# FPGA_SDRAM_bank.net
KiCad netlist of a schematic drawn in Altium Designer
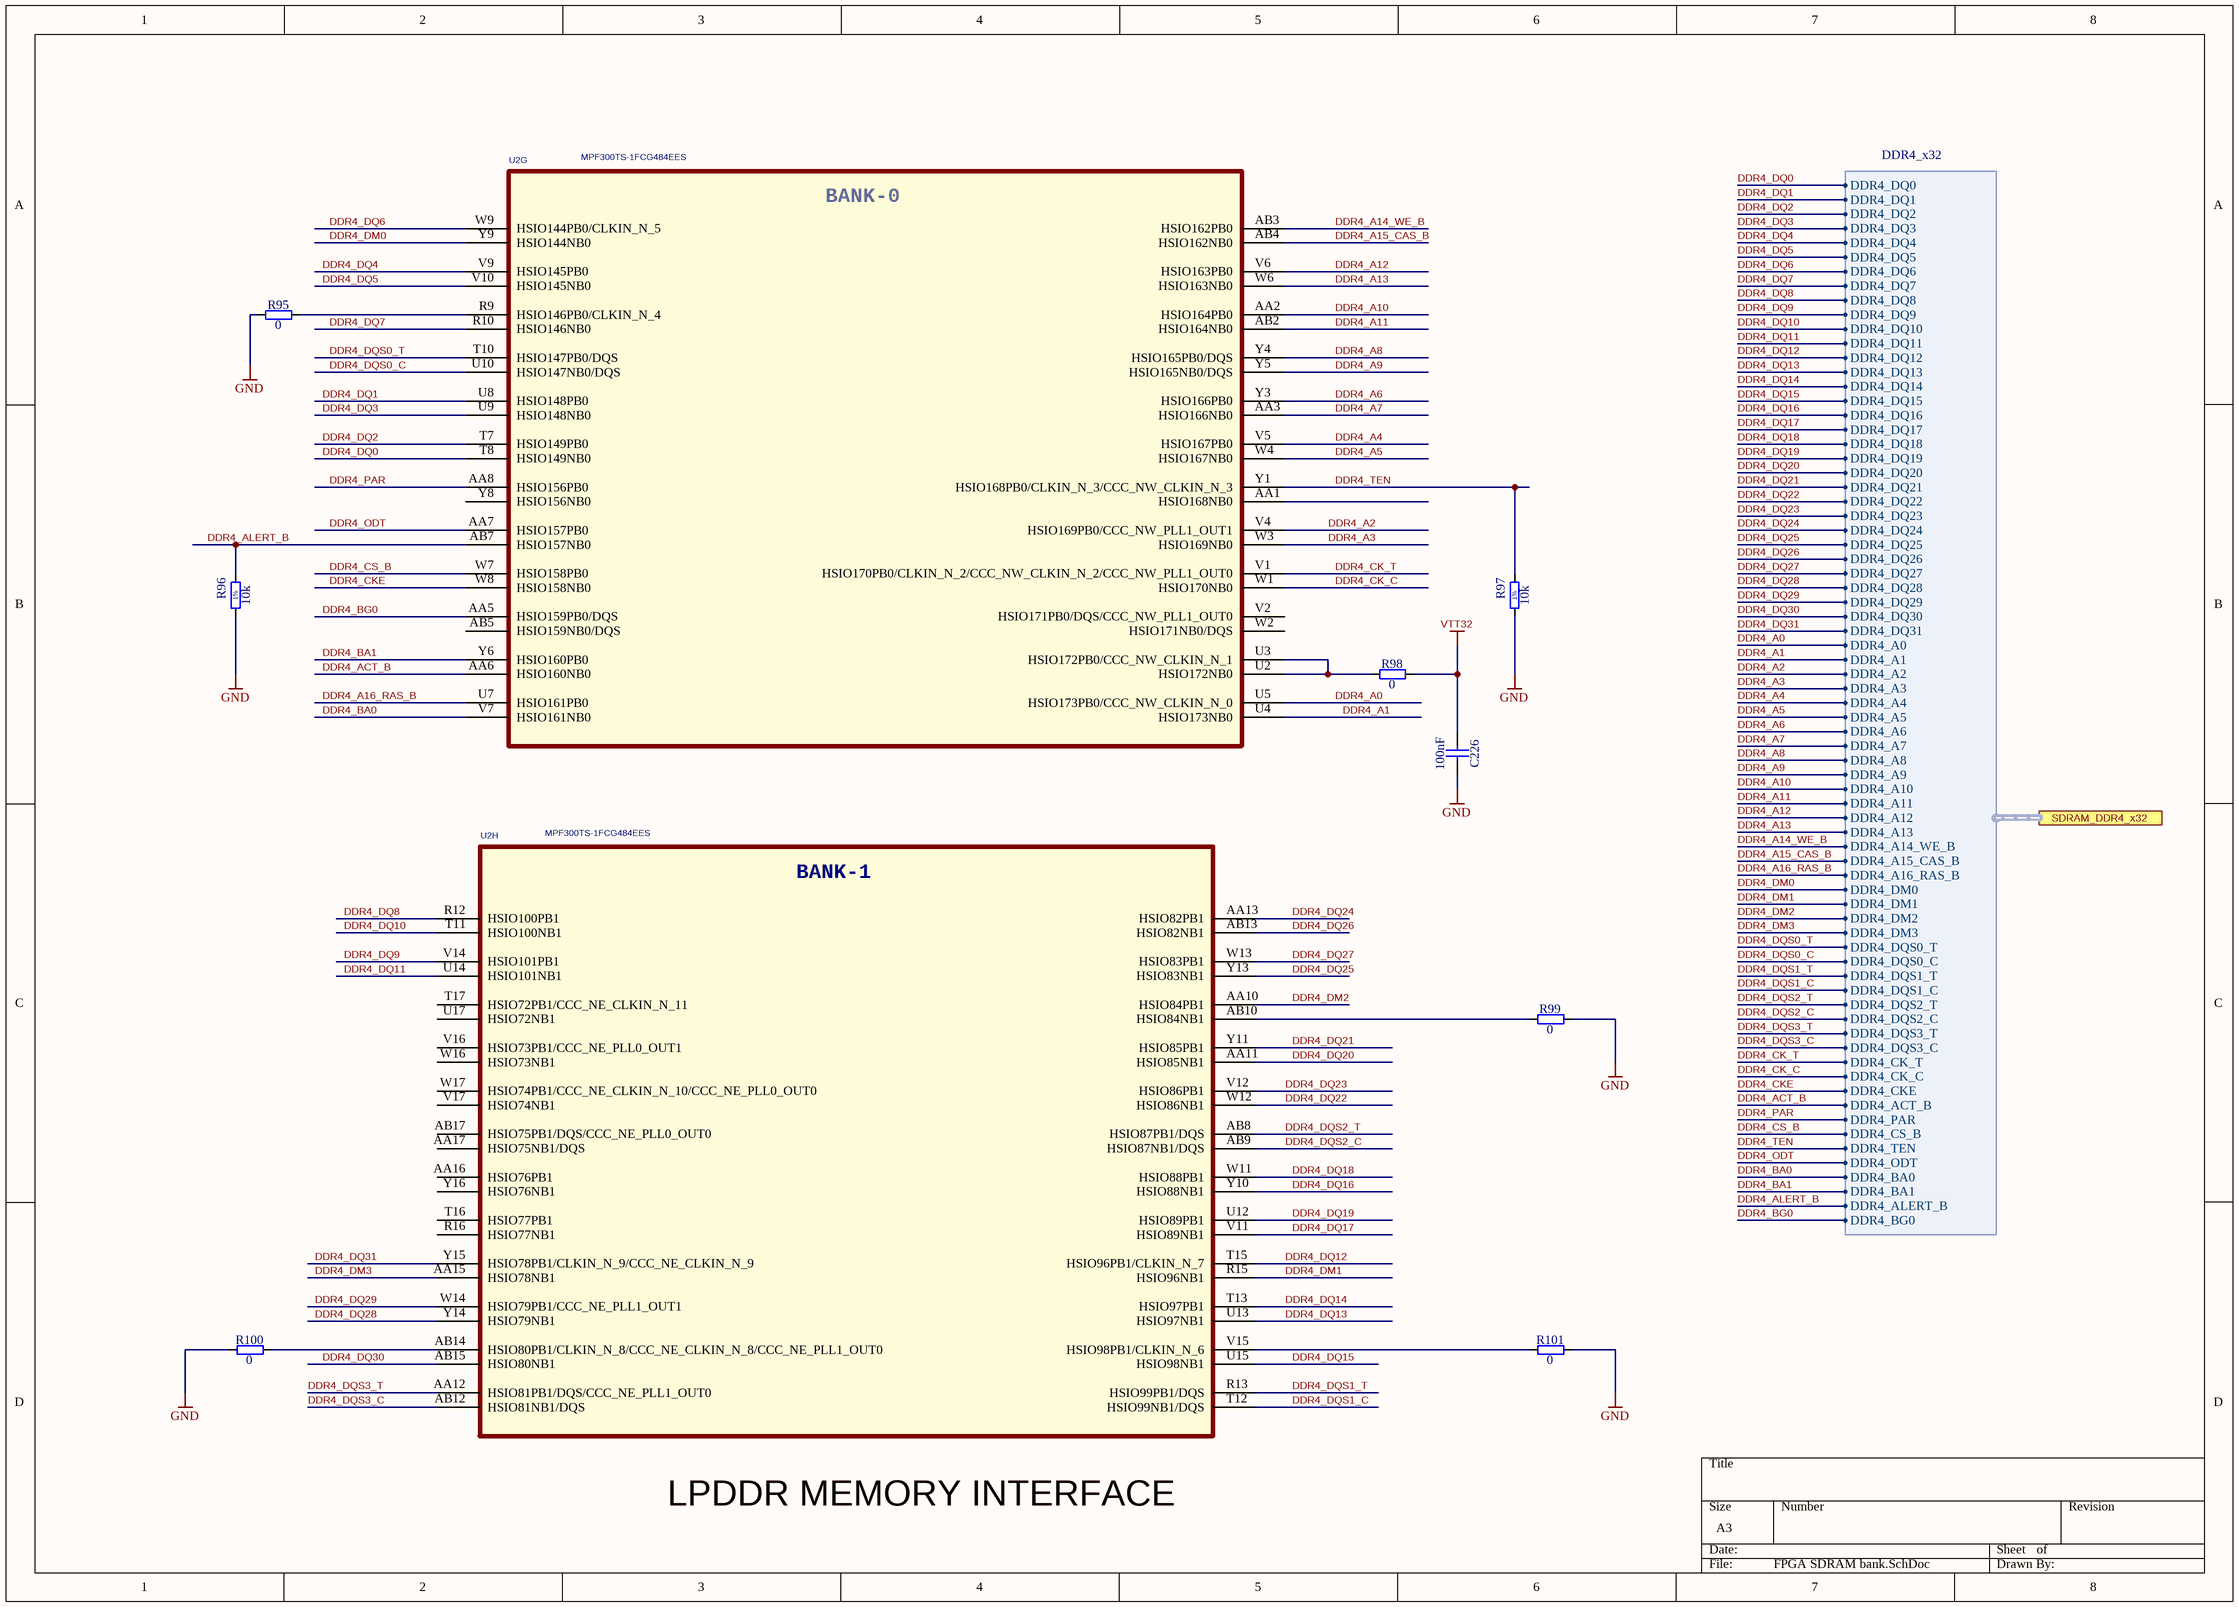
[diagram p0: FPGA SDRAM bank.SchDoc]

(export (version "E")
  (design (tool "Eeschema 10.0.6"))
  (components
    (comp (ref "C226")
      (value "100nF")
      (footprint "CAPC0603X33N")
      (description "Non-polarised capacitor")
      (fields
        (field (name "MANUFACTURER PART NUMBER") "CC0201_100NF_6.3V_10%_X5R")
        (field (name "MANUFACTURER") "GENERIC")
        (field (name "AUTHOR") "CERN DEM JLC")
      )
      (libsource (lib "Capacitors") (part "Capacitor - non polarized"))
    )
    (comp (ref "R95")
      (value "0")
      (footprint "RESC1005X40N")
      (description "Resistor")
      (fields
        (field (name "PART NUMBER") "R0402_0R_JUMPER")
        (field (name "MANUFACTURER") "GENERIC")
        (field (name "AUTHOR") "CERN DEM JLC")
      )
      (libsource (lib "Resistors") (part "Resistor"))
    )
    (comp (ref "R96")
      (value "10k")
      (footprint "RESC1005X40N")
      (description "Resistor - 1%")
      (fields
        (field (name "MANUFACTURER PART NUMBER") "R0402_10K_1%_0.0625W_100PPM")
        (field (name "MANUFACTURER") "GENERIC")
        (field (name "AUTHOR") "CERN DEM JLC")
      )
      (libsource (lib "Resistors") (part "Resistor - 1%"))
    )
    (comp (ref "R97")
      (value "10k")
      (footprint "RESC1005X40N")
      (description "Resistor - 1%")
      (fields
        (field (name "MANUFACTURER PART NUMBER") "R0402_10K_1%_0.0625W_100PPM")
        (field (name "MANUFACTURER") "GENERIC")
        (field (name "AUTHOR") "CERN DEM JLC")
      )
      (libsource (lib "Resistors") (part "Resistor - 1%"))
    )
    (comp (ref "R98")
      (value "0")
      (footprint "RESC1005X40N")
      (description "Resistor")
      (fields
        (field (name "PART NUMBER") "R0402_0R_JUMPER")
        (field (name "MANUFACTURER") "GENERIC")
        (field (name "AUTHOR") "CERN DEM JLC")
      )
      (libsource (lib "Resistors") (part "Resistor"))
    )
    (comp (ref "R99")
      (value "0")
      (footprint "RESC1005X40N")
      (description "Resistor")
      (fields
        (field (name "PART NUMBER") "R0402_0R_JUMPER")
        (field (name "MANUFACTURER") "GENERIC")
        (field (name "AUTHOR") "CERN DEM JLC")
      )
      (libsource (lib "Resistors") (part "Resistor"))
    )
    (comp (ref "R100")
      (value "0")
      (footprint "RESC1005X40N")
      (description "Resistor")
      (fields
        (field (name "PART NUMBER") "R0402_0R_JUMPER")
        (field (name "MANUFACTURER") "GENERIC")
        (field (name "AUTHOR") "CERN DEM JLC")
      )
      (libsource (lib "Resistors") (part "Resistor"))
    )
    (comp (ref "R101")
      (value "0")
      (footprint "RESC1005X40N")
      (description "Resistor")
      (fields
        (field (name "PART NUMBER") "R0402_0R_JUMPER")
        (field (name "MANUFACTURER") "GENERIC")
        (field (name "AUTHOR") "CERN DEM JLC")
      )
      (libsource (lib "Resistors") (part "Resistor"))
    )
    (comp (ref "U2")
      (value "MPF300TS-1FCG484EES")
      (footprint "BGA484C100P22X22_2300X2300X320")
      (description "FCG484,23mmX23mm,1.0mm pitch")
      (fields (field (name "MANUFACTURER") "Microsemi") (field (name "PART NUMBER") "MPF300TS-1FCG484I"))
      (libsource (lib "LIBRARY_SCH") (part "FPGA_MPF300T-FCG484"))
    )
  )
  (nets
    (net (code "2") (name "/DDR4_A0") (class "Default")
      (node (ref "U2") (pin "U5") (pinfunction "HSIO173PB0/CCC_NW_CLKIN_N_0_U5") (pintype "passive"))
    )
    (net (code "3") (name "/DDR4_A1") (class "Default")
      (node (ref "U2") (pin "U4") (pinfunction "HSIO173NB0_U4") (pintype "passive"))
    )
    (net (code "4") (name "/DDR4_A2") (class "Default")
      (node (ref "U2") (pin "V4") (pinfunction "HSIO169PB0/CCC_NW_PLL1_OUT1_V4") (pintype "passive"))
    )
    (net (code "5") (name "/DDR4_A3") (class "Default")
      (node (ref "U2") (pin "W3") (pinfunction "HSIO169NB0_W3") (pintype "passive"))
    )
    (net (code "6") (name "/DDR4_A4") (class "Default")
      (node (ref "U2") (pin "V5") (pinfunction "HSIO167PB0_V5") (pintype "passive"))
    )
    (net (code "7") (name "/DDR4_A5") (class "Default")
      (node (ref "U2") (pin "W4") (pinfunction "HSIO167NB0_W4") (pintype "passive"))
    )
    (net (code "8") (name "/DDR4_A6") (class "Default")
      (node (ref "U2") (pin "Y3") (pinfunction "HSIO166PB0_Y3") (pintype "passive"))
    )
    (net (code "9") (name "/DDR4_A7") (class "Default")
      (node (ref "U2") (pin "AA3") (pinfunction "HSIO166NB0_AA3") (pintype "passive"))
    )
    (net (code "10") (name "/DDR4_A8") (class "Default")
      (node (ref "U2") (pin "Y4") (pinfunction "HSIO165PB0/DQS_Y4") (pintype "passive"))
    )
    (net (code "11") (name "/DDR4_A9") (class "Default")
      (node (ref "U2") (pin "Y5") (pinfunction "HSIO165NB0/DQS_Y5") (pintype "passive"))
    )
    (net (code "12") (name "/DDR4_A10") (class "Default")
      (node (ref "U2") (pin "AA2") (pinfunction "HSIO164PB0_AA2") (pintype "passive"))
    )
    (net (code "13") (name "/DDR4_A11") (class "Default")
      (node (ref "U2") (pin "AB2") (pinfunction "HSIO164NB0_AB2") (pintype "passive"))
    )
    (net (code "14") (name "/DDR4_A12") (class "Default")
      (node (ref "U2") (pin "V6") (pinfunction "HSIO163PB0_V6") (pintype "passive"))
    )
    (net (code "15") (name "/DDR4_A13") (class "Default")
      (node (ref "U2") (pin "W6") (pinfunction "HSIO163NB0_W6") (pintype "passive"))
    )
    (net (code "16") (name "/DDR4_A14_WE_B") (class "Default")
      (node (ref "U2") (pin "AB3") (pinfunction "HSIO162PB0_AB3") (pintype "passive"))
    )
    (net (code "17") (name "/DDR4_A15_CAS_B") (class "Default")
      (node (ref "U2") (pin "AB4") (pinfunction "HSIO162NB0_AB4") (pintype "passive"))
    )
    (net (code "18") (name "/DDR4_A16_RAS_B") (class "Default")
      (node (ref "U2") (pin "U7") (pinfunction "HSIO161PB0_U7") (pintype "passive"))
    )
    (net (code "19") (name "/DDR4_ACT_B") (class "Default")
      (node (ref "U2") (pin "AA6") (pinfunction "HSIO160NB0_AA6") (pintype "passive"))
    )
    (net (code "20") (name "/DDR4_ALERT_B") (class "Default")
      (node (ref "R96") (pin "2") (pinfunction "2_2") (pintype "passive"))
      (node (ref "U2") (pin "AB7") (pinfunction "HSIO157NB0_AB7") (pintype "passive"))
    )
    (net (code "21") (name "/DDR4_BA0") (class "Default")
      (node (ref "U2") (pin "V7") (pinfunction "HSIO161NB0_V7") (pintype "passive"))
    )
    (net (code "22") (name "/DDR4_BA1") (class "Default")
      (node (ref "U2") (pin "Y6") (pinfunction "HSIO160PB0_Y6") (pintype "passive"))
    )
    (net (code "23") (name "/DDR4_BG0") (class "Default")
      (node (ref "U2") (pin "AA5") (pinfunction "HSIO159PB0/DQS_AA5") (pintype "passive"))
    )
    (net (code "24") (name "/DDR4_CKE") (class "Default")
      (node (ref "U2") (pin "W8") (pinfunction "HSIO158NB0_W8") (pintype "passive"))
    )
    (net (code "25") (name "/DDR4_CK_C") (class "Default")
      (node (ref "U2") (pin "W1") (pinfunction "HSIO170NB0_W1") (pintype "passive"))
    )
    (net (code "26") (name "/DDR4_CK_T") (class "Default")
      (node (ref "U2") (pin "V1") (pinfunction "HSIO170PB0/CLKIN_N_2/CCC_NW_CLKIN_N_2/CCC_NW_PLL1_OUT0_V1") (pintype "passive"))
    )
    (net (code "27") (name "/DDR4_CS_B") (class "Default")
      (node (ref "U2") (pin "W7") (pinfunction "HSIO158PB0_W7") (pintype "passive"))
    )
    (net (code "28") (name "/DDR4_DM0") (class "Default")
      (node (ref "U2") (pin "Y9") (pinfunction "HSIO144NB0_Y9") (pintype "passive"))
    )
    (net (code "29") (name "/DDR4_DM1") (class "Default")
      (node (ref "U2") (pin "R15") (pinfunction "HSIO96NB1_R15") (pintype "passive"))
    )
    (net (code "30") (name "/DDR4_DM2") (class "Default")
      (node (ref "U2") (pin "AA10") (pinfunction "HSIO84PB1_AA10") (pintype "passive"))
    )
    (net (code "31") (name "/DDR4_DM3") (class "Default")
      (node (ref "U2") (pin "AA15") (pinfunction "HSIO78NB1_AA15") (pintype "passive"))
    )
    (net (code "32") (name "/DDR4_DQ0") (class "Default")
      (node (ref "U2") (pin "T8") (pinfunction "HSIO149NB0_T8") (pintype "passive"))
    )
    (net (code "33") (name "/DDR4_DQ1") (class "Default")
      (node (ref "U2") (pin "U8") (pinfunction "HSIO148PB0_U8") (pintype "passive"))
    )
    (net (code "34") (name "/DDR4_DQ2") (class "Default")
      (node (ref "U2") (pin "T7") (pinfunction "HSIO149PB0_T7") (pintype "passive"))
    )
    (net (code "35") (name "/DDR4_DQ3") (class "Default")
      (node (ref "U2") (pin "U9") (pinfunction "HSIO148NB0_U9") (pintype "passive"))
    )
    (net (code "36") (name "/DDR4_DQ4") (class "Default")
      (node (ref "U2") (pin "V9") (pinfunction "HSIO145PB0_V9") (pintype "passive"))
    )
    (net (code "37") (name "/DDR4_DQ5") (class "Default")
      (node (ref "U2") (pin "V10") (pinfunction "HSIO145NB0_V10") (pintype "passive"))
    )
    (net (code "38") (name "/DDR4_DQ6") (class "Default")
      (node (ref "U2") (pin "W9") (pinfunction "HSIO144PB0/CLKIN_N_5_W9") (pintype "passive"))
    )
    (net (code "39") (name "/DDR4_DQ7") (class "Default")
      (node (ref "U2") (pin "R10") (pinfunction "HSIO146NB0_R10") (pintype "passive"))
    )
    (net (code "40") (name "/DDR4_DQ8") (class "Default")
      (node (ref "U2") (pin "R12") (pinfunction "HSIO100PB1_R12") (pintype "passive"))
    )
    (net (code "41") (name "/DDR4_DQ9") (class "Default")
      (node (ref "U2") (pin "V14") (pinfunction "HSIO101PB1_V14") (pintype "passive"))
    )
    (net (code "42") (name "/DDR4_DQ10") (class "Default")
      (node (ref "U2") (pin "T11") (pinfunction "HSIO100NB1_T11") (pintype "passive"))
    )
    (net (code "43") (name "/DDR4_DQ11") (class "Default")
      (node (ref "U2") (pin "U14") (pinfunction "HSIO101NB1_U14") (pintype "passive"))
    )
    (net (code "44") (name "/DDR4_DQ12") (class "Default")
      (node (ref "U2") (pin "T15") (pinfunction "HSIO96PB1/CLKIN_N_7_T15") (pintype "passive"))
    )
    (net (code "45") (name "/DDR4_DQ13") (class "Default")
      (node (ref "U2") (pin "U13") (pinfunction "HSIO97NB1_U13") (pintype "passive"))
    )
    (net (code "46") (name "/DDR4_DQ14") (class "Default")
      (node (ref "U2") (pin "T13") (pinfunction "HSIO97PB1_T13") (pintype "passive"))
    )
    (net (code "47") (name "/DDR4_DQ15") (class "Default")
      (node (ref "U2") (pin "U15") (pinfunction "HSIO98NB1_U15") (pintype "passive"))
    )
    (net (code "48") (name "/DDR4_DQ16") (class "Default")
      (node (ref "U2") (pin "Y10") (pinfunction "HSIO88NB1_Y10") (pintype "passive"))
    )
    (net (code "49") (name "/DDR4_DQ17") (class "Default")
      (node (ref "U2") (pin "V11") (pinfunction "HSIO89NB1_V11") (pintype "passive"))
    )
    (net (code "50") (name "/DDR4_DQ18") (class "Default")
      (node (ref "U2") (pin "W11") (pinfunction "HSIO88PB1_W11") (pintype "passive"))
    )
    (net (code "51") (name "/DDR4_DQ19") (class "Default")
      (node (ref "U2") (pin "U12") (pinfunction "HSIO89PB1_U12") (pintype "passive"))
    )
    (net (code "52") (name "/DDR4_DQ20") (class "Default")
      (node (ref "U2") (pin "AA11") (pinfunction "HSIO85NB1_AA11") (pintype "passive"))
    )
    (net (code "53") (name "/DDR4_DQ21") (class "Default")
      (node (ref "U2") (pin "Y11") (pinfunction "HSIO85PB1_Y11") (pintype "passive"))
    )
    (net (code "54") (name "/DDR4_DQ22") (class "Default")
      (node (ref "U2") (pin "W12") (pinfunction "HSIO86NB1_W12") (pintype "passive"))
    )
    (net (code "55") (name "/DDR4_DQ23") (class "Default")
      (node (ref "U2") (pin "V12") (pinfunction "HSIO86PB1_V12") (pintype "passive"))
    )
    (net (code "56") (name "/DDR4_DQ24") (class "Default")
      (node (ref "U2") (pin "AA13") (pinfunction "HSIO82PB1_AA13") (pintype "passive"))
    )
    (net (code "57") (name "/DDR4_DQ25") (class "Default")
      (node (ref "U2") (pin "Y13") (pinfunction "HSIO83NB1_Y13") (pintype "passive"))
    )
    (net (code "58") (name "/DDR4_DQ26") (class "Default")
      (node (ref "U2") (pin "AB13") (pinfunction "HSIO82NB1_AB13") (pintype "passive"))
    )
    (net (code "59") (name "/DDR4_DQ27") (class "Default")
      (node (ref "U2") (pin "W13") (pinfunction "HSIO83PB1_W13") (pintype "passive"))
    )
    (net (code "60") (name "/DDR4_DQ28") (class "Default")
      (node (ref "U2") (pin "Y14") (pinfunction "HSIO79NB1_Y14") (pintype "passive"))
    )
    (net (code "61") (name "/DDR4_DQ29") (class "Default")
      (node (ref "U2") (pin "W14") (pinfunction "HSIO79PB1/CCC_NE_PLL1_OUT1_W14") (pintype "passive"))
    )
    (net (code "62") (name "/DDR4_DQ30") (class "Default")
      (node (ref "U2") (pin "AB15") (pinfunction "HSIO80NB1_AB15") (pintype "passive"))
    )
    (net (code "63") (name "/DDR4_DQ31") (class "Default")
      (node (ref "U2") (pin "Y15") (pinfunction "HSIO78PB1/CLKIN_N_9/CCC_NE_CLKIN_N_9_Y15") (pintype "passive"))
    )
    (net (code "64") (name "/DDR4_DQS0_C") (class "Default")
      (node (ref "U2") (pin "U10") (pinfunction "HSIO147NB0/DQS_U10") (pintype "passive"))
    )
    (net (code "65") (name "/DDR4_DQS0_T") (class "Default")
      (node (ref "U2") (pin "T10") (pinfunction "HSIO147PB0/DQS_T10") (pintype "passive"))
    )
    (net (code "66") (name "/DDR4_DQS1_C") (class "Default")
      (node (ref "U2") (pin "T12") (pinfunction "HSIO99NB1/DQS_T12") (pintype "passive"))
    )
    (net (code "67") (name "/DDR4_DQS1_T") (class "Default")
      (node (ref "U2") (pin "R13") (pinfunction "HSIO99PB1/DQS_R13") (pintype "passive"))
    )
    (net (code "68") (name "/DDR4_DQS2_C") (class "Default")
      (node (ref "U2") (pin "AB9") (pinfunction "HSIO87NB1/DQS_AB9") (pintype "passive"))
    )
    (net (code "69") (name "/DDR4_DQS2_T") (class "Default")
      (node (ref "U2") (pin "AB8") (pinfunction "HSIO87PB1/DQS_AB8") (pintype "passive"))
    )
    (net (code "70") (name "/DDR4_DQS3_C") (class "Default")
      (node (ref "U2") (pin "AB12") (pinfunction "HSIO81NB1/DQS_AB12") (pintype "passive"))
    )
    (net (code "71") (name "/DDR4_DQS3_T") (class "Default")
      (node (ref "U2") (pin "AA12") (pinfunction "HSIO81PB1/DQS/CCC_NE_PLL1_OUT0_AA12") (pintype "passive"))
    )
    (net (code "72") (name "/DDR4_ODT") (class "Default")
      (node (ref "U2") (pin "AA7") (pinfunction "HSIO157PB0_AA7") (pintype "passive"))
    )
    (net (code "73") (name "/DDR4_PAR") (class "Default")
      (node (ref "U2") (pin "AA8") (pinfunction "HSIO156PB0_AA8") (pintype "passive"))
    )
    (net (code "74") (name "/DDR4_TEN") (class "Default")
      (node (ref "R97") (pin "2") (pinfunction "2_2") (pintype "passive"))
      (node (ref "U2") (pin "Y1") (pinfunction "HSIO168PB0/CLKIN_N_3/CCC_NW_CLKIN_N_3_Y1") (pintype "passive"))
    )
    (net (code "76") (name "GND") (class "Default")
      (node (ref "C226") (pin "2") (pinfunction "2_2") (pintype "passive"))
      (node (ref "R100") (pin "1") (pinfunction "1_1") (pintype "passive"))
      (node (ref "R101") (pin "2") (pinfunction "2_2") (pintype "passive"))
      (node (ref "R95") (pin "1") (pinfunction "1_1") (pintype "passive"))
      (node (ref "R96") (pin "1") (pinfunction "1_1") (pintype "passive"))
      (node (ref "R97") (pin "1") (pinfunction "1_1") (pintype "passive"))
      (node (ref "R99") (pin "2") (pinfunction "2_2") (pintype "passive"))
    )
    (net (code "77") (name "Net-(U2G-HSIO146PB0{slash}CLKIN_N_4)") (class "Default")
      (node (ref "R95") (pin "2") (pinfunction "2_2") (pintype "passive"))
      (node (ref "U2") (pin "R9") (pinfunction "HSIO146PB0/CLKIN_N_4_R9") (pintype "passive"))
    )
    (net (code "78") (name "Net-(U2G-HSIO172NB0)") (class "Default")
      (node (ref "R98") (pin "1") (pinfunction "1_1") (pintype "passive"))
      (node (ref "U2") (pin "U2") (pinfunction "HSIO172NB0_U2") (pintype "passive"))
      (node (ref "U2") (pin "U3") (pinfunction "HSIO172PB0/CCC_NW_CLKIN_N_1_U3") (pintype "passive"))
    )
    (net (code "79") (name "Net-(U2H-HSIO80PB1{slash}CLKIN_N_8{slash}CCC_NE_CLKIN_N_8{slash}CCC_NE_PLL1_OUT0)") (class "Default")
      (node (ref "R100") (pin "2") (pinfunction "2_2") (pintype "passive"))
      (node (ref "U2") (pin "AB14") (pinfunction "HSIO80PB1/CLKIN_N_8/CCC_NE_CLKIN_N_8/CCC_NE_PLL1_OUT0_AB14") (pintype "passive"))
    )
    (net (code "80") (name "Net-(U2H-HSIO84NB1)") (class "Default")
      (node (ref "R99") (pin "1") (pinfunction "1_1") (pintype "passive"))
      (node (ref "U2") (pin "AB10") (pinfunction "HSIO84NB1_AB10") (pintype "passive"))
    )
    (net (code "81") (name "Net-(U2H-HSIO98PB1{slash}CLKIN_N_6)") (class "Default")
      (node (ref "R101") (pin "1") (pinfunction "1_1") (pintype "passive"))
      (node (ref "U2") (pin "V15") (pinfunction "HSIO98PB1/CLKIN_N_6_V15") (pintype "passive"))
    )
    (net (code "82") (name "VTT32") (class "Default")
      (node (ref "C226") (pin "1") (pinfunction "1_1") (pintype "passive"))
      (node (ref "R98") (pin "2") (pinfunction "2_2") (pintype "passive"))
    )
    (net (code "83") (name "unconnected-(U2G-HSIO156NB0-PadY8)") (class "Default")
      (node (ref "U2") (pin "Y8") (pinfunction "HSIO156NB0_Y8") (pintype "passive"))
    )
    (net (code "84") (name "unconnected-(U2G-HSIO159NB0{slash}DQS-PadAB5)") (class "Default")
      (node (ref "U2") (pin "AB5") (pinfunction "HSIO159NB0/DQS_AB5") (pintype "passive"))
    )
    (net (code "85") (name "unconnected-(U2G-HSIO168NB0-PadAA1)") (class "Default")
      (node (ref "U2") (pin "AA1") (pinfunction "HSIO168NB0_AA1") (pintype "passive"))
    )
    (net (code "86") (name "unconnected-(U2G-HSIO171NB0{slash}DQS-PadW2)") (class "Default")
      (node (ref "U2") (pin "W2") (pinfunction "HSIO171NB0/DQS_W2") (pintype "passive"))
    )
    (net (code "87") (name "unconnected-(U2G-HSIO171PB0{slash}DQS{slash}CCC_NW_PLL1_OUT0-PadV2)") (class "Default")
      (node (ref "U2") (pin "V2") (pinfunction "HSIO171PB0/DQS/CCC_NW_PLL1_OUT0_V2") (pintype "passive"))
    )
    (net (code "88") (name "unconnected-(U2H-HSIO72NB1-PadU17)") (class "Default")
      (node (ref "U2") (pin "U17") (pinfunction "HSIO72NB1_U17") (pintype "passive"))
    )
    (net (code "89") (name "unconnected-(U2H-HSIO72PB1{slash}CCC_NE_CLKIN_N_11-PadT17)") (class "Default")
      (node (ref "U2") (pin "T17") (pinfunction "HSIO72PB1/CCC_NE_CLKIN_N_11_T17") (pintype "passive"))
    )
    (net (code "90") (name "unconnected-(U2H-HSIO73NB1-PadW16)") (class "Default")
      (node (ref "U2") (pin "W16") (pinfunction "HSIO73NB1_W16") (pintype "passive"))
    )
    (net (code "91") (name "unconnected-(U2H-HSIO73PB1{slash}CCC_NE_PLL0_OUT1-PadV16)") (class "Default")
      (node (ref "U2") (pin "V16") (pinfunction "HSIO73PB1/CCC_NE_PLL0_OUT1_V16") (pintype "passive"))
    )
    (net (code "92") (name "unconnected-(U2H-HSIO74NB1-PadV17)") (class "Default")
      (node (ref "U2") (pin "V17") (pinfunction "HSIO74NB1_V17") (pintype "passive"))
    )
    (net (code "93") (name "unconnected-(U2H-HSIO74PB1{slash}CCC_NE_CLKIN_N_10{slash}CCC_NE_PLL0_OUT0-PadW17)") (class "Default")
      (node (ref "U2") (pin "W17") (pinfunction "HSIO74PB1/CCC_NE_CLKIN_N_10/CCC_NE_PLL0_OUT0_W17") (pintype "passive"))
    )
    (net (code "94") (name "unconnected-(U2H-HSIO75NB1{slash}DQS-PadAA17)") (class "Default")
      (node (ref "U2") (pin "AA17") (pinfunction "HSIO75NB1/DQS_AA17") (pintype "passive"))
    )
    (net (code "95") (name "unconnected-(U2H-HSIO75PB1{slash}DQS{slash}CCC_NE_PLL0_OUT0-PadAB17)") (class "Default")
      (node (ref "U2") (pin "AB17") (pinfunction "HSIO75PB1/DQS/CCC_NE_PLL0_OUT0_AB17") (pintype "passive"))
    )
    (net (code "96") (name "unconnected-(U2H-HSIO76NB1-PadY16)") (class "Default")
      (node (ref "U2") (pin "Y16") (pinfunction "HSIO76NB1_Y16") (pintype "passive"))
    )
    (net (code "97") (name "unconnected-(U2H-HSIO76PB1-PadAA16)") (class "Default")
      (node (ref "U2") (pin "AA16") (pinfunction "HSIO76PB1_AA16") (pintype "passive"))
    )
    (net (code "98") (name "unconnected-(U2H-HSIO77NB1-PadR16)") (class "Default")
      (node (ref "U2") (pin "R16") (pinfunction "HSIO77NB1_R16") (pintype "passive"))
    )
    (net (code "99") (name "unconnected-(U2H-HSIO77PB1-PadT16)") (class "Default")
      (node (ref "U2") (pin "T16") (pinfunction "HSIO77PB1_T16") (pintype "passive"))
    )
  )
)
